# MaixCAMPort.net
KiCad netlist of a schematic drawn in Altium Designer
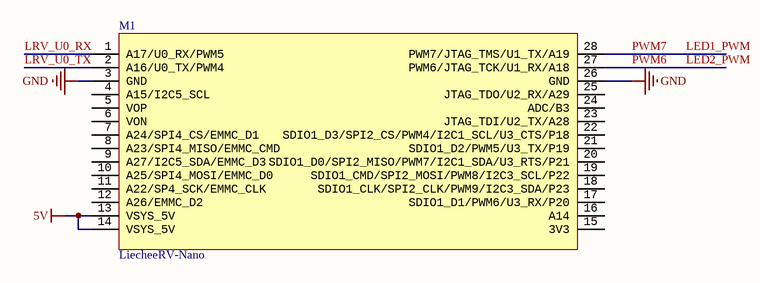
[diagram p0: MaixCAMPort.SchDoc]

(export (version "E")
  (design (tool "Eeschema 10.0.6"))
  (components
    (comp (ref "M1")
      (value "LiecheeRV-Nano")
      (footprint "LicheeRV-Nano(SDIO_NC)-半孔探针")
      (description "Sipeed MaixCAM模块")
      (libsource (lib "13.1 - 模块") (part "LiecheeRV-Nano"))
    )
  )
  (nets
    (net (code "1") (name "/LED1_PWM") (class "Default")
      (node (ref "M1") (pin "28") (pinfunction "PWM7/JTAG_TMS/U1_TX/A19_28") (pintype "passive"))
    )
    (net (code "2") (name "/LED2_PWM") (class "Default")
      (node (ref "M1") (pin "27") (pinfunction "PWM6/JTAG_TCK/U1_RX/A18_27") (pintype "passive"))
    )
    (net (code "3") (name "/LRV_U0_RX") (class "Default")
      (node (ref "M1") (pin "1") (pinfunction "A17/U0_RX/PWM5_1") (pintype "passive"))
    )
    (net (code "4") (name "/LRV_U0_TX") (class "Default")
      (node (ref "M1") (pin "2") (pinfunction "A16/U0_TX/PWM4_2") (pintype "passive"))
    )
    (net (code "5") (name "5V") (class "Default")
      (node (ref "M1") (pin "13") (pinfunction "VSYS_5V_13") (pintype "passive"))
      (node (ref "M1") (pin "14") (pinfunction "VSYS_5V_14") (pintype "passive"))
    )
    (net (code "6") (name "GND") (class "Default")
      (node (ref "M1") (pin "26") (pinfunction "GND_26") (pintype "passive"))
      (node (ref "M1") (pin "3") (pinfunction "GND_3") (pintype "passive"))
    )
    (net (code "7") (name "unconnected-(M1-3V3-Pad15)") (class "Default")
      (node (ref "M1") (pin "15") (pinfunction "3V3_15") (pintype "passive"))
    )
    (net (code "8") (name "unconnected-(M1-A14-Pad16)") (class "Default")
      (node (ref "M1") (pin "16") (pinfunction "A14_16") (pintype "passive"))
    )
    (net (code "9") (name "unconnected-(M1-A15{slash}I2C5_SCL-Pad4)") (class "Default")
      (node (ref "M1") (pin "4") (pinfunction "A15/I2C5_SCL_4") (pintype "passive"))
    )
    (net (code "10") (name "unconnected-(M1-A22{slash}SP4_SCK{slash}EMMC_CLK-Pad11)") (class "Default")
      (node (ref "M1") (pin "11") (pinfunction "A22/SP4_SCK/EMMC_CLK_11") (pintype "passive"))
    )
    (net (code "11") (name "unconnected-(M1-A23{slash}SPI4_MISO{slash}EMMC_CMD-Pad8)") (class "Default")
      (node (ref "M1") (pin "8") (pinfunction "A23/SPI4_MISO/EMMC_CMD_8") (pintype "passive"))
    )
    (net (code "12") (name "unconnected-(M1-A24{slash}SPI4_CS{slash}EMMC_D1-Pad7)") (class "Default")
      (node (ref "M1") (pin "7") (pinfunction "A24/SPI4_CS/EMMC_D1_7") (pintype "passive"))
    )
    (net (code "13") (name "unconnected-(M1-A25{slash}SPI4_MOSI{slash}EMMC_D0-Pad10)") (class "Default")
      (node (ref "M1") (pin "10") (pinfunction "A25/SPI4_MOSI/EMMC_D0_10") (pintype "passive"))
    )
    (net (code "14") (name "unconnected-(M1-A26{slash}EMMC_D2-Pad12)") (class "Default")
      (node (ref "M1") (pin "12") (pinfunction "A26/EMMC_D2_12") (pintype "passive"))
    )
    (net (code "15") (name "unconnected-(M1-A27{slash}I2C5_SDA{slash}EMMC_D3-Pad9)") (class "Default")
      (node (ref "M1") (pin "9") (pinfunction "A27/I2C5_SDA/EMMC_D3_9") (pintype "passive"))
    )
    (net (code "16") (name "unconnected-(M1-ADC{slash}B3-Pad24)") (class "Default")
      (node (ref "M1") (pin "24") (pinfunction "ADC/B3_24") (pintype "passive"))
    )
    (net (code "17") (name "unconnected-(M1-JTAG_TDI{slash}U2_TX{slash}A28-Pad23)") (class "Default")
      (node (ref "M1") (pin "23") (pinfunction "JTAG_TDI/U2_TX/A28_23") (pintype "passive"))
    )
    (net (code "18") (name "unconnected-(M1-JTAG_TDO{slash}U2_RX{slash}A29-Pad25)") (class "Default")
      (node (ref "M1") (pin "25") (pinfunction "JTAG_TDO/U2_RX/A29_25") (pintype "passive"))
    )
    (net (code "19") (name "unconnected-(M1-SDIO1_CLK{slash}SPI2_CLK{slash}PWM9{slash}I2C3_SDA{slash}P23-Pad18)") (class "Default")
      (node (ref "M1") (pin "18") (pinfunction "SDIO1_CLK/SPI2_CLK/PWM9/I2C3_SDA/P23_18") (pintype "passive"))
    )
    (net (code "20") (name "unconnected-(M1-SDIO1_CMD{slash}SPI2_MOSI{slash}PWM8{slash}I2C3_SCL{slash}P22-Pad19)") (class "Default")
      (node (ref "M1") (pin "19") (pinfunction "SDIO1_CMD/SPI2_MOSI/PWM8/I2C3_SCL/P22_19") (pintype "passive"))
    )
    (net (code "21") (name "unconnected-(M1-SDIO1_D0{slash}SPI2_MISO{slash}PWM7{slash}I2C1_SDA{slash}U3_RTS{slash}P21-Pad20)") (class "Default")
      (node (ref "M1") (pin "20") (pinfunction "SDIO1_D0/SPI2_MISO/PWM7/I2C1_SDA/U3_RTS/P21_20") (pintype "passive"))
    )
    (net (code "22") (name "unconnected-(M1-SDIO1_D1{slash}PWM6{slash}U3_RX{slash}P20-Pad17)") (class "Default")
      (node (ref "M1") (pin "17") (pinfunction "SDIO1_D1/PWM6/U3_RX/P20_17") (pintype "passive"))
    )
    (net (code "23") (name "unconnected-(M1-SDIO1_D2{slash}PWM5{slash}U3_TX{slash}P19-Pad21)") (class "Default")
      (node (ref "M1") (pin "21") (pinfunction "SDIO1_D2/PWM5/U3_TX/P19_21") (pintype "passive"))
    )
    (net (code "24") (name "unconnected-(M1-SDIO1_D3{slash}SPI2_CS{slash}PWM4{slash}I2C1_SCL{slash}U3_CTS{slash}P18-Pad22)") (class "Default")
      (node (ref "M1") (pin "22") (pinfunction "SDIO1_D3/SPI2_CS/PWM4/I2C1_SCL/U3_CTS/P18_22") (pintype "passive"))
    )
    (net (code "25") (name "unconnected-(M1-VON-Pad6)") (class "Default")
      (node (ref "M1") (pin "6") (pinfunction "VON_6") (pintype "passive"))
    )
    (net (code "26") (name "unconnected-(M1-VOP-Pad5)") (class "Default")
      (node (ref "M1") (pin "5") (pinfunction "VOP_5") (pintype "passive"))
    )
  )
)
